# easyedadiagrama.net
KiCad netlist of a schematic drawn in EasyEDA
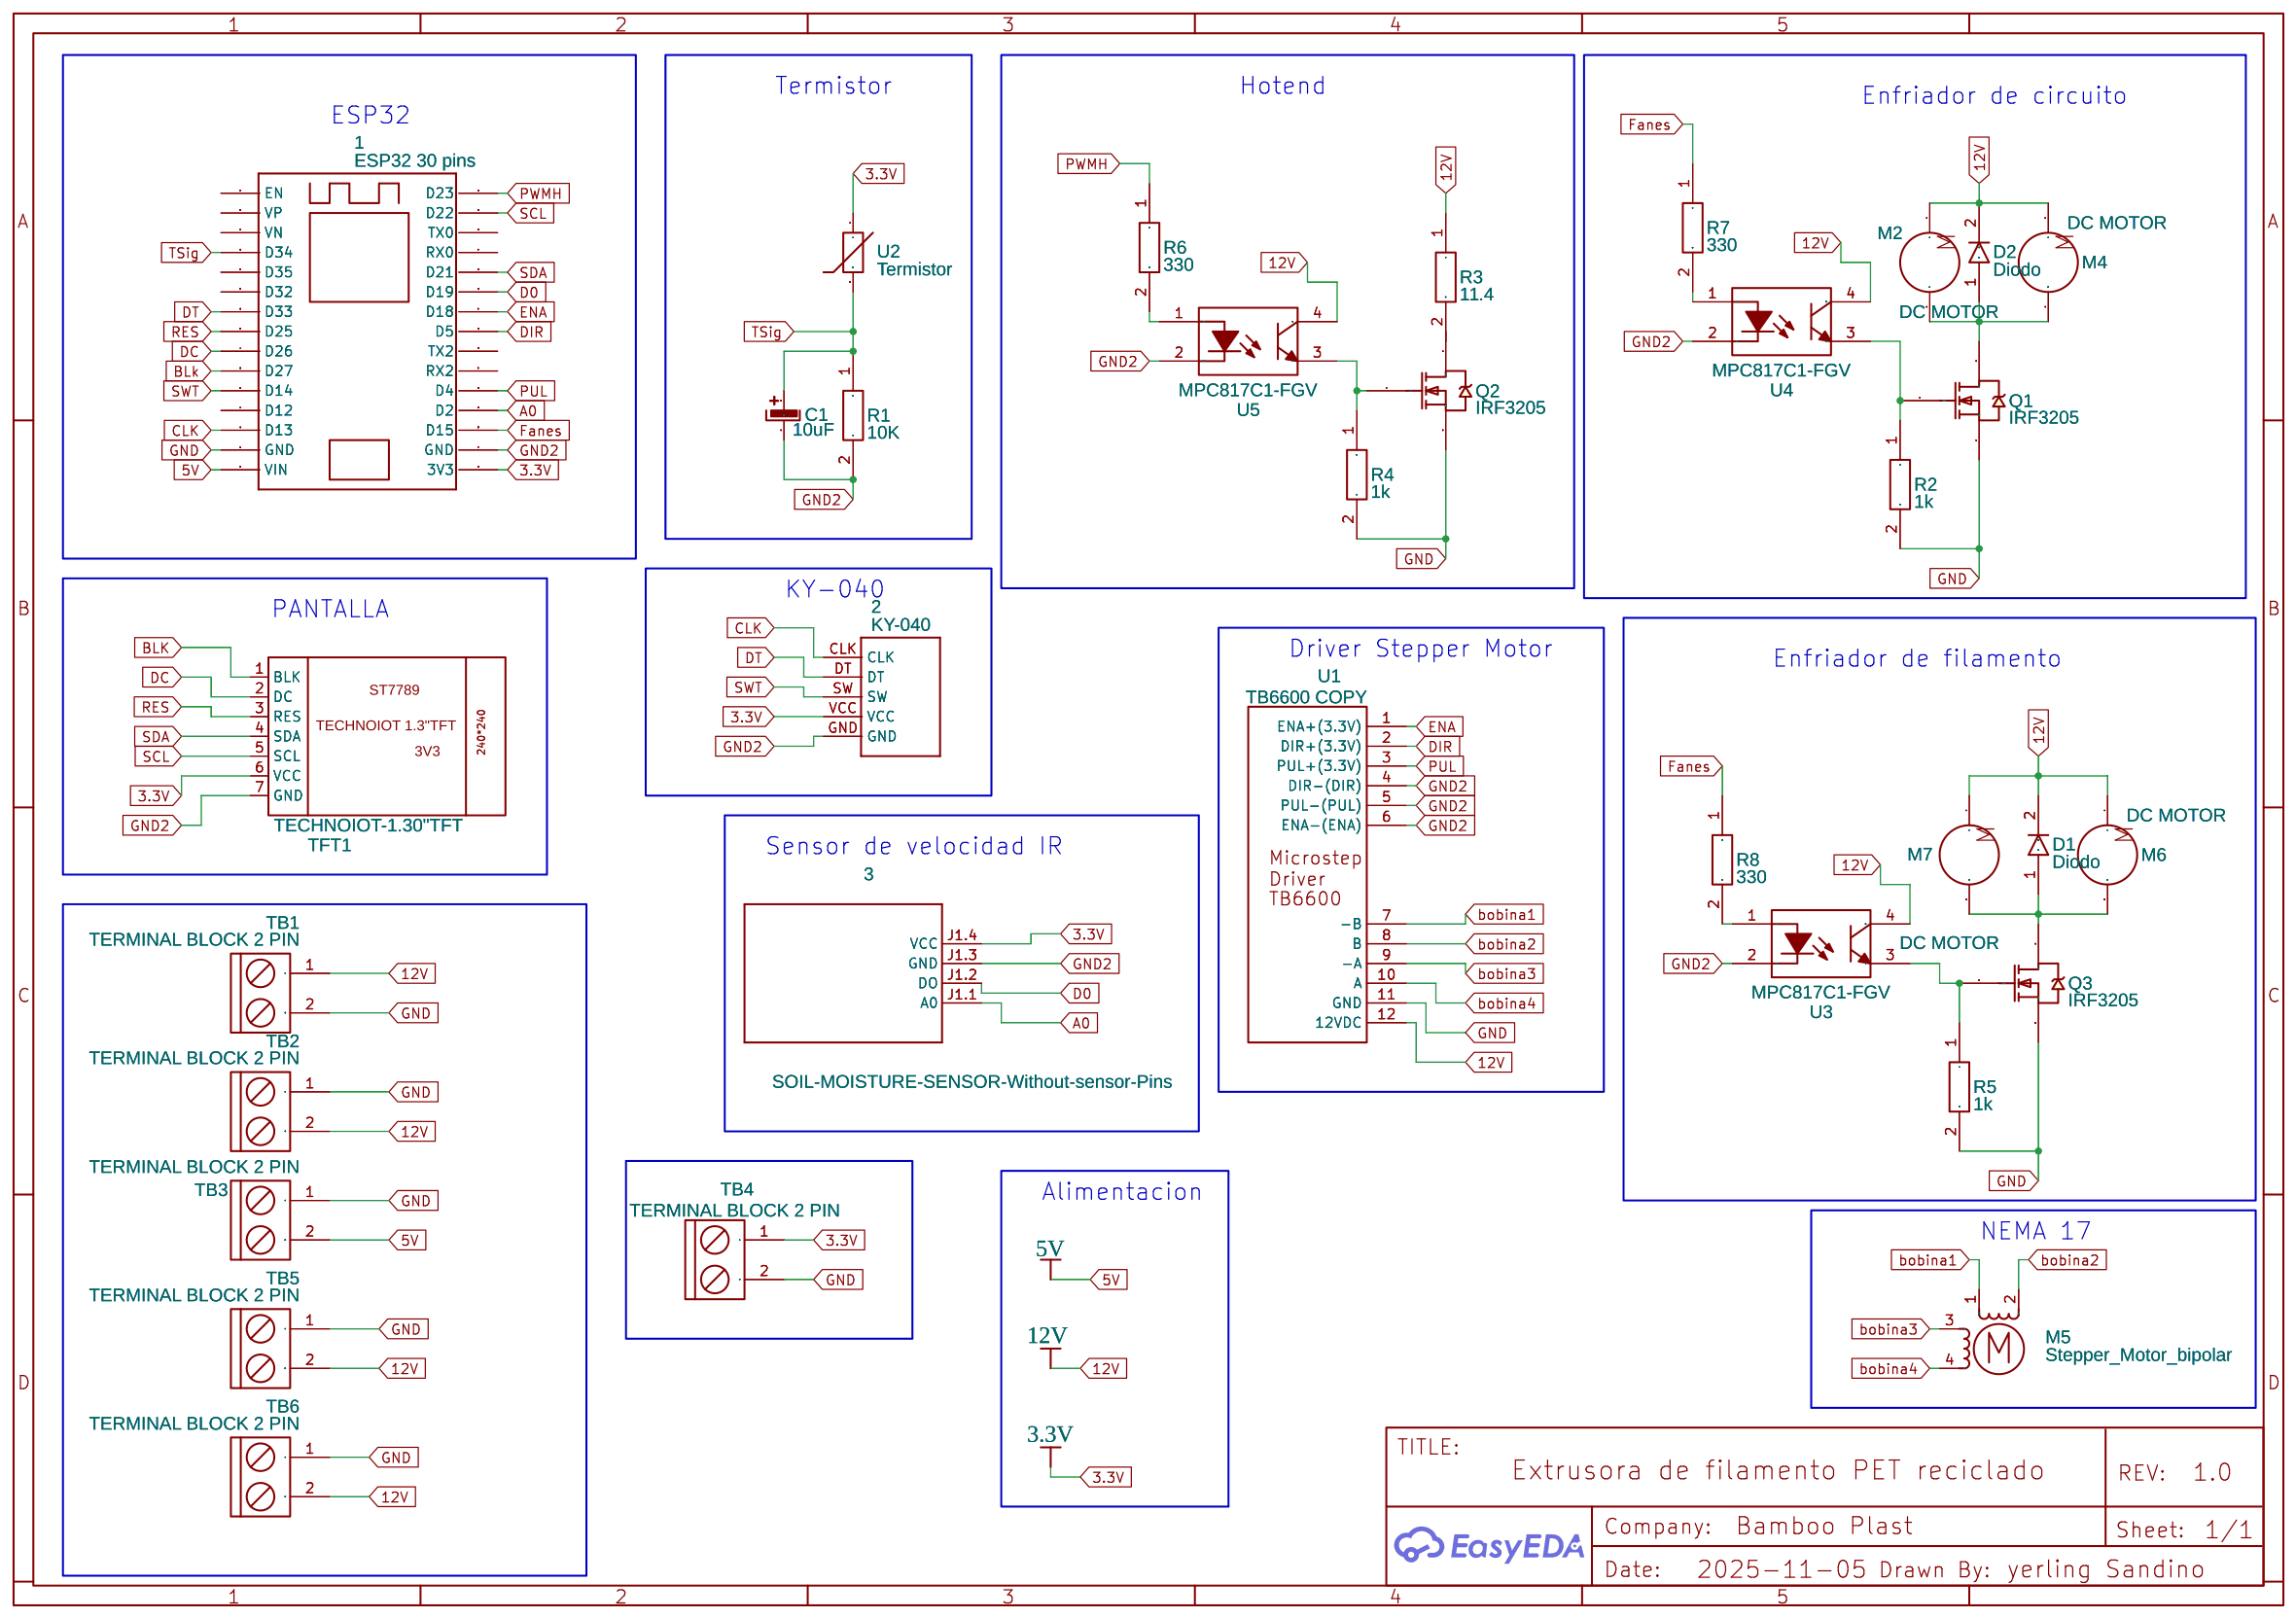
[diagram p0: schematic sheet]

(export (version "E")
  (design (tool "Eeschema 10.0.6"))
  (components
    (comp (ref "1") (value "ESP32 30 pins") (libsource (lib "") (part "ESP32 30 pins")))
    (comp (ref "2") (value "KY-040") (libsource (lib "") (part "KY-040")))
    (comp (ref "3")
      (value "SOIL-MOISTURE-SENSOR-Without-sensor-Pins")
      (libsource (lib "") (part "SOIL-MOISTURE-SENSOR-Without-sensor-Pins"))
    )
    (comp (ref "C1") (value "10uF") (libsource (lib "") (part "CONDENSADOR")))
    (comp (ref "D1") (value "Diodo") (libsource (lib "") (part "Diodo")))
    (comp (ref "D2") (value "Diodo") (libsource (lib "") (part "Diodo")))
    (comp (ref "M2") (value "DC MOTOR") (libsource (lib "") (part "DC MOTOR")))
    (comp (ref "M4") (value "DC MOTOR") (libsource (lib "") (part "DC MOTOR")))
    (comp (ref "M5") (value "Stepper_Motor_bipolar") (libsource (lib "") (part "Stepper_Motor_bipolar")))
    (comp (ref "M6") (value "DC MOTOR") (libsource (lib "") (part "DC MOTOR")))
    (comp (ref "M7") (value "DC MOTOR") (libsource (lib "") (part "DC MOTOR")))
    (comp (ref "Q1") (value "IRF3205") (libsource (lib "") (part "IRF3205")))
    (comp (ref "Q2") (value "IRF3205") (libsource (lib "") (part "IRF3205")))
    (comp (ref "Q3") (value "IRF3205") (libsource (lib "") (part "IRF3205")))
    (comp (ref "R1") (value "10K") (libsource (lib "") (part "Resistencia")))
    (comp (ref "R2") (value "1k") (libsource (lib "") (part "Resistencia")))
    (comp (ref "R3") (value "11.4") (libsource (lib "") (part "Resistencia")))
    (comp (ref "R4") (value "1k") (libsource (lib "") (part "Resistencia")))
    (comp (ref "R5") (value "1k") (libsource (lib "") (part "Resistencia")))
    (comp (ref "R6") (value "330") (libsource (lib "") (part "Resistencia")))
    (comp (ref "R7") (value "330") (libsource (lib "") (part "Resistencia")))
    (comp (ref "R8") (value "330") (libsource (lib "") (part "Resistencia")))
    (comp (ref "TB1")
      (value "TERMINAL BLOCK 2 PIN")
      (fields
        (field (name "Manufacturer Part") "OSTTC020162")
        (field (name "Manufacturer") "On Shore Technology Inc.")
      )
      (libsource (lib "") (part "TERMINAL BLOCK 2 PIN"))
    )
    (comp (ref "TB2")
      (value "TERMINAL BLOCK 2 PIN")
      (fields
        (field (name "Manufacturer Part") "OSTTC020162")
        (field (name "Manufacturer") "On Shore Technology Inc.")
      )
      (libsource (lib "") (part "TERMINAL BLOCK 2 PIN"))
    )
    (comp (ref "TB3")
      (value "TERMINAL BLOCK 2 PIN")
      (fields
        (field (name "Manufacturer Part") "OSTTC020162")
        (field (name "Manufacturer") "On Shore Technology Inc.")
      )
      (libsource (lib "") (part "TERMINAL BLOCK 2 PIN"))
    )
    (comp (ref "TB4")
      (value "TERMINAL BLOCK 2 PIN")
      (fields
        (field (name "Manufacturer Part") "OSTTC020162")
        (field (name "Manufacturer") "On Shore Technology Inc.")
      )
      (libsource (lib "") (part "TERMINAL BLOCK 2 PIN"))
    )
    (comp (ref "TB5")
      (value "TERMINAL BLOCK 2 PIN")
      (fields
        (field (name "Manufacturer Part") "OSTTC020162")
        (field (name "Manufacturer") "On Shore Technology Inc.")
      )
      (libsource (lib "") (part "TERMINAL BLOCK 2 PIN"))
    )
    (comp (ref "TB6")
      (value "TERMINAL BLOCK 2 PIN")
      (fields
        (field (name "Manufacturer Part") "OSTTC020162")
        (field (name "Manufacturer") "On Shore Technology Inc.")
      )
      (libsource (lib "") (part "TERMINAL BLOCK 2 PIN"))
    )
    (comp (ref "TFT1")
      (value "TECHNOIOT-1.30\"TFT")
      (libsource (lib "") (part "TECHNOIOT-1.30{dblquote}TFT"))
    )
    (comp (ref "U1") (value "TB6600 COPY") (libsource (lib "") (part "TB6600 COPY")))
    (comp (ref "U2") (value "Termistor") (libsource (lib "") (part "Termistor")))
    (comp (ref "U3")
      (value "MPC817C1-FGV")
      (fields (field (name "Manufacturer") "MP(美禄科技)"))
      (libsource (lib "") (part "MPC817C1-FGV"))
    )
    (comp (ref "U4")
      (value "MPC817C1-FGV")
      (fields (field (name "Manufacturer") "MP(美禄科技)"))
      (libsource (lib "") (part "MPC817C1-FGV"))
    )
    (comp (ref "U5")
      (value "MPC817C1-FGV")
      (fields (field (name "Manufacturer") "MP(美禄科技)"))
      (libsource (lib "") (part "MPC817C1-FGV"))
    )
  )
  (nets
    (net (code "1") (name "3.3V") (class "Default")
      (node (ref "1") (pin "16") (pinfunction "3V3_16") (pintype "bidirectional"))
      (node (ref "2") (pin "VCC") (pinfunction "VCC_VCC") (pintype "bidirectional"))
      (node (ref "3") (pin "J1.4") (pinfunction "VCC_J1.4") (pintype "bidirectional"))
      (node (ref "TB4") (pin "1") (pinfunction "1_1") (pintype "unspecified"))
      (node (ref "TFT1") (pin "6") (pinfunction "VCC_6") (pintype "bidirectional"))
      (node (ref "U2") (pin "1") (pinfunction "1_1") (pintype "unspecified"))
    )
    (net (code "2") (name "5V") (class "Default")
      (node (ref "1") (pin "1") (pinfunction "VIN_1") (pintype "bidirectional"))
      (node (ref "TB3") (pin "2") (pinfunction "2_2") (pintype "unspecified"))
    )
    (net (code "3") (name "12V") (class "Default")
      (node (ref "D1") (pin "2") (pinfunction "2_2") (pintype "unspecified"))
      (node (ref "D2") (pin "2") (pinfunction "2_2") (pintype "unspecified"))
      (node (ref "M2") (pin "1") (pinfunction "1_1") (pintype "unspecified"))
      (node (ref "M4") (pin "1") (pinfunction "1_1") (pintype "unspecified"))
      (node (ref "M6") (pin "1") (pinfunction "1_1") (pintype "unspecified"))
      (node (ref "M7") (pin "1") (pinfunction "1_1") (pintype "unspecified"))
      (node (ref "R3") (pin "1") (pinfunction "1_1") (pintype "unspecified"))
      (node (ref "TB1") (pin "1") (pinfunction "1_1") (pintype "unspecified"))
      (node (ref "TB2") (pin "2") (pinfunction "2_2") (pintype "unspecified"))
      (node (ref "TB5") (pin "2") (pinfunction "2_2") (pintype "unspecified"))
      (node (ref "TB6") (pin "2") (pinfunction "2_2") (pintype "unspecified"))
      (node (ref "U1") (pin "12") (pinfunction "12VDC_12") (pintype "unspecified"))
      (node (ref "U3") (pin "4") (pinfunction "C_4") (pintype "unspecified"))
      (node (ref "U4") (pin "4") (pinfunction "C_4") (pintype "unspecified"))
      (node (ref "U5") (pin "4") (pinfunction "C_4") (pintype "unspecified"))
    )
    (net (code "4") (name "A0") (class "Default")
      (node (ref "1") (pin "19") (pinfunction "D2_19") (pintype "bidirectional"))
      (node (ref "3") (pin "J1.1") (pinfunction "A0_J1.1") (pintype "bidirectional"))
    )
    (net (code "5") (name "BLK") (class "Default")
      (node (ref "TFT1") (pin "1") (pinfunction "BLK_1") (pintype "bidirectional"))
    )
    (net (code "6") (name "BLk") (class "Default")
      (node (ref "1") (pin "6") (pinfunction "D27_6") (pintype "bidirectional"))
    )
    (net (code "7") (name "CLK") (class "Default")
      (node (ref "1") (pin "3") (pinfunction "D13_3") (pintype "bidirectional"))
      (node (ref "2") (pin "CLK") (pinfunction "CLK_CLK") (pintype "bidirectional"))
    )
    (net (code "8") (name "D0") (class "Default")
      (node (ref "1") (pin "25") (pinfunction "D19_25") (pintype "bidirectional"))
      (node (ref "3") (pin "J1.2") (pinfunction "DO_J1.2") (pintype "bidirectional"))
    )
    (net (code "9") (name "DC") (class "Default")
      (node (ref "1") (pin "7") (pinfunction "D26_7") (pintype "bidirectional"))
      (node (ref "TFT1") (pin "2") (pinfunction "DC_2") (pintype "bidirectional"))
    )
    (net (code "10") (name "DIR") (class "Default")
      (node (ref "1") (pin "23") (pinfunction "D5_23") (pintype "bidirectional"))
      (node (ref "U1") (pin "2") (pinfunction "DIR+(3.3V)_2") (pintype "unspecified"))
    )
    (net (code "11") (name "DT") (class "Default")
      (node (ref "1") (pin "9") (pinfunction "D33_9") (pintype "bidirectional"))
      (node (ref "2") (pin "DT") (pinfunction "DT_DT") (pintype "bidirectional"))
    )
    (net (code "12") (name "ENA") (class "Default")
      (node (ref "1") (pin "24") (pinfunction "D18_24") (pintype "bidirectional"))
      (node (ref "U1") (pin "1") (pinfunction "ENA+(3.3V)_1") (pintype "unspecified"))
    )
    (net (code "13") (name "Fanes") (class "Default")
      (node (ref "1") (pin "18") (pinfunction "D15_18") (pintype "bidirectional"))
      (node (ref "R7") (pin "1") (pinfunction "1_1") (pintype "unspecified"))
      (node (ref "R8") (pin "1") (pinfunction "1_1") (pintype "unspecified"))
    )
    (net (code "14") (name "GND") (class "Default")
      (node (ref "1") (pin "2") (pinfunction "GND_2") (pintype "bidirectional"))
      (node (ref "Q1") (pin "3") (pinfunction "S_3") (pintype "unspecified"))
      (node (ref "Q2") (pin "3") (pinfunction "S_3") (pintype "unspecified"))
      (node (ref "Q3") (pin "3") (pinfunction "S_3") (pintype "unspecified"))
      (node (ref "R2") (pin "2") (pinfunction "2_2") (pintype "unspecified"))
      (node (ref "R4") (pin "2") (pinfunction "2_2") (pintype "unspecified"))
      (node (ref "R5") (pin "2") (pinfunction "2_2") (pintype "unspecified"))
      (node (ref "TB1") (pin "2") (pinfunction "2_2") (pintype "unspecified"))
      (node (ref "TB2") (pin "1") (pinfunction "1_1") (pintype "unspecified"))
      (node (ref "TB3") (pin "1") (pinfunction "1_1") (pintype "unspecified"))
      (node (ref "TB4") (pin "2") (pinfunction "2_2") (pintype "unspecified"))
      (node (ref "TB5") (pin "1") (pinfunction "1_1") (pintype "unspecified"))
      (node (ref "TB6") (pin "1") (pinfunction "1_1") (pintype "unspecified"))
      (node (ref "U1") (pin "11") (pinfunction "GND_11") (pintype "unspecified"))
    )
    (net (code "15") (name "GND2") (class "Default")
      (node (ref "1") (pin "17") (pinfunction "GND_17") (pintype "bidirectional"))
      (node (ref "2") (pin "GND") (pinfunction "GND_GND") (pintype "bidirectional"))
      (node (ref "3") (pin "J1.3") (pinfunction "GND_J1.3") (pintype "bidirectional"))
      (node (ref "C1") (pin "2") (pinfunction "2_2") (pintype "unspecified"))
      (node (ref "R1") (pin "2") (pinfunction "2_2") (pintype "unspecified"))
      (node (ref "TFT1") (pin "7") (pinfunction "GND_7") (pintype "bidirectional"))
      (node (ref "U1") (pin "4") (pinfunction "DIR-(DIR)_4") (pintype "unspecified"))
      (node (ref "U1") (pin "5") (pinfunction "PUL-(PUL)_5") (pintype "unspecified"))
      (node (ref "U1") (pin "6") (pinfunction "ENA-(ENA)_6") (pintype "unspecified"))
      (node (ref "U3") (pin "2") (pinfunction "C_2") (pintype "unspecified"))
      (node (ref "U4") (pin "2") (pinfunction "C_2") (pintype "unspecified"))
      (node (ref "U5") (pin "2") (pinfunction "C_2") (pintype "unspecified"))
    )
    (net (code "16") (name "Net-(Q1-D)") (class "Default")
      (node (ref "D2") (pin "1") (pinfunction "1_1") (pintype "unspecified"))
      (node (ref "M2") (pin "2") (pinfunction "2_2") (pintype "unspecified"))
      (node (ref "M4") (pin "2") (pinfunction "2_2") (pintype "unspecified"))
      (node (ref "Q1") (pin "2") (pinfunction "D_2") (pintype "unspecified"))
    )
    (net (code "17") (name "Net-(Q1-G)") (class "Default")
      (node (ref "Q1") (pin "1") (pinfunction "G_1") (pintype "unspecified"))
      (node (ref "R2") (pin "1") (pinfunction "1_1") (pintype "unspecified"))
      (node (ref "U4") (pin "3") (pinfunction "E_3") (pintype "unspecified"))
    )
    (net (code "18") (name "Net-(Q2-D)") (class "Default")
      (node (ref "Q2") (pin "2") (pinfunction "D_2") (pintype "unspecified"))
      (node (ref "R3") (pin "2") (pinfunction "2_2") (pintype "unspecified"))
    )
    (net (code "19") (name "Net-(Q2-G)") (class "Default")
      (node (ref "Q2") (pin "1") (pinfunction "G_1") (pintype "unspecified"))
      (node (ref "R4") (pin "1") (pinfunction "1_1") (pintype "unspecified"))
      (node (ref "U5") (pin "3") (pinfunction "E_3") (pintype "unspecified"))
    )
    (net (code "20") (name "Net-(Q3-D)") (class "Default")
      (node (ref "D1") (pin "1") (pinfunction "1_1") (pintype "unspecified"))
      (node (ref "M6") (pin "2") (pinfunction "2_2") (pintype "unspecified"))
      (node (ref "M7") (pin "2") (pinfunction "2_2") (pintype "unspecified"))
      (node (ref "Q3") (pin "2") (pinfunction "D_2") (pintype "unspecified"))
    )
    (net (code "21") (name "Net-(Q3-G)") (class "Default")
      (node (ref "Q3") (pin "1") (pinfunction "G_1") (pintype "unspecified"))
      (node (ref "R5") (pin "1") (pinfunction "1_1") (pintype "unspecified"))
      (node (ref "U3") (pin "3") (pinfunction "E_3") (pintype "unspecified"))
    )
    (net (code "22") (name "Net-(U3-A)") (class "Default")
      (node (ref "R8") (pin "2") (pinfunction "2_2") (pintype "unspecified"))
      (node (ref "U3") (pin "1") (pinfunction "A_1") (pintype "unspecified"))
    )
    (net (code "23") (name "Net-(U4-A)") (class "Default")
      (node (ref "R7") (pin "2") (pinfunction "2_2") (pintype "unspecified"))
      (node (ref "U4") (pin "1") (pinfunction "A_1") (pintype "unspecified"))
    )
    (net (code "24") (name "Net-(U5-A)") (class "Default")
      (node (ref "R6") (pin "2") (pinfunction "2_2") (pintype "unspecified"))
      (node (ref "U5") (pin "1") (pinfunction "A_1") (pintype "unspecified"))
    )
    (net (code "25") (name "PUL") (class "Default")
      (node (ref "1") (pin "20") (pinfunction "D4_20") (pintype "bidirectional"))
      (node (ref "U1") (pin "3") (pinfunction "PUL+(3.3V)_3") (pintype "unspecified"))
    )
    (net (code "26") (name "PWMH") (class "Default")
      (node (ref "1") (pin "30") (pinfunction "D23_30") (pintype "bidirectional"))
      (node (ref "R6") (pin "1") (pinfunction "1_1") (pintype "unspecified"))
    )
    (net (code "27") (name "RES") (class "Default")
      (node (ref "1") (pin "8") (pinfunction "D25_8") (pintype "bidirectional"))
      (node (ref "TFT1") (pin "3") (pinfunction "RES_3") (pintype "bidirectional"))
    )
    (net (code "28") (name "SCL") (class "Default")
      (node (ref "1") (pin "29") (pinfunction "D22_29") (pintype "bidirectional"))
      (node (ref "TFT1") (pin "5") (pinfunction "SCL_5") (pintype "bidirectional"))
    )
    (net (code "29") (name "SDA") (class "Default")
      (node (ref "1") (pin "26") (pinfunction "D21_26") (pintype "bidirectional"))
      (node (ref "TFT1") (pin "4") (pinfunction "SDA_4") (pintype "bidirectional"))
    )
    (net (code "30") (name "SWT") (class "Default")
      (node (ref "1") (pin "5") (pinfunction "D14_5") (pintype "bidirectional"))
      (node (ref "2") (pin "SW") (pinfunction "SW_SW") (pintype "bidirectional"))
    )
    (net (code "31") (name "TSig") (class "Default")
      (node (ref "1") (pin "12") (pinfunction "D34_12") (pintype "bidirectional"))
      (node (ref "C1") (pin "1") (pinfunction "1_1") (pintype "unspecified"))
      (node (ref "R1") (pin "1") (pinfunction "1_1") (pintype "unspecified"))
      (node (ref "U2") (pin "2") (pinfunction "2_2") (pintype "unspecified"))
    )
    (net (code "32") (name "bobina1") (class "Default")
      (node (ref "M5") (pin "1") (pinfunction "1_1") (pintype "unspecified"))
      (node (ref "U1") (pin "7") (pinfunction "-B_7") (pintype "unspecified"))
    )
    (net (code "33") (name "bobina2") (class "Default")
      (node (ref "M5") (pin "2") (pinfunction "2_2") (pintype "unspecified"))
      (node (ref "U1") (pin "8") (pinfunction "B_8") (pintype "unspecified"))
    )
    (net (code "34") (name "bobina3") (class "Default")
      (node (ref "M5") (pin "3") (pinfunction "3_3") (pintype "unspecified"))
      (node (ref "U1") (pin "9") (pinfunction "-A_9") (pintype "unspecified"))
    )
    (net (code "35") (name "bobina4") (class "Default")
      (node (ref "M5") (pin "4") (pinfunction "4_4") (pintype "unspecified"))
      (node (ref "U1") (pin "10") (pinfunction "A_10") (pintype "unspecified"))
    )
    (net (code "36") (name "unconnected-(1-D12-Pad4)") (class "Default")
      (node (ref "1") (pin "4") (pinfunction "D12_4") (pintype "bidirectional"))
    )
    (net (code "37") (name "unconnected-(1-D32-Pad10)") (class "Default")
      (node (ref "1") (pin "10") (pinfunction "D32_10") (pintype "bidirectional"))
    )
    (net (code "38") (name "unconnected-(1-D35-Pad11)") (class "Default")
      (node (ref "1") (pin "11") (pinfunction "D35_11") (pintype "bidirectional"))
    )
    (net (code "39") (name "unconnected-(1-EN-Pad15)") (class "Default")
      (node (ref "1") (pin "15") (pinfunction "EN_15") (pintype "bidirectional"))
    )
    (net (code "40") (name "unconnected-(1-RX0-Pad27)") (class "Default")
      (node (ref "1") (pin "27") (pinfunction "RX0_27") (pintype "bidirectional"))
    )
    (net (code "41") (name "unconnected-(1-RX2-Pad21)") (class "Default")
      (node (ref "1") (pin "21") (pinfunction "RX2_21") (pintype "bidirectional"))
    )
    (net (code "42") (name "unconnected-(1-TX0-Pad28)") (class "Default")
      (node (ref "1") (pin "28") (pinfunction "TX0_28") (pintype "bidirectional"))
    )
    (net (code "43") (name "unconnected-(1-TX2-Pad22)") (class "Default")
      (node (ref "1") (pin "22") (pinfunction "TX2_22") (pintype "bidirectional"))
    )
    (net (code "44") (name "unconnected-(1-VN-Pad13)") (class "Default")
      (node (ref "1") (pin "13") (pinfunction "VN_13") (pintype "bidirectional"))
    )
    (net (code "45") (name "unconnected-(1-VP-Pad14)") (class "Default")
      (node (ref "1") (pin "14") (pinfunction "VP_14") (pintype "bidirectional"))
    )
  )
)
